# BMS-banana-rev1-0.net
KiCad netlist of a schematic drawn in EAGLE
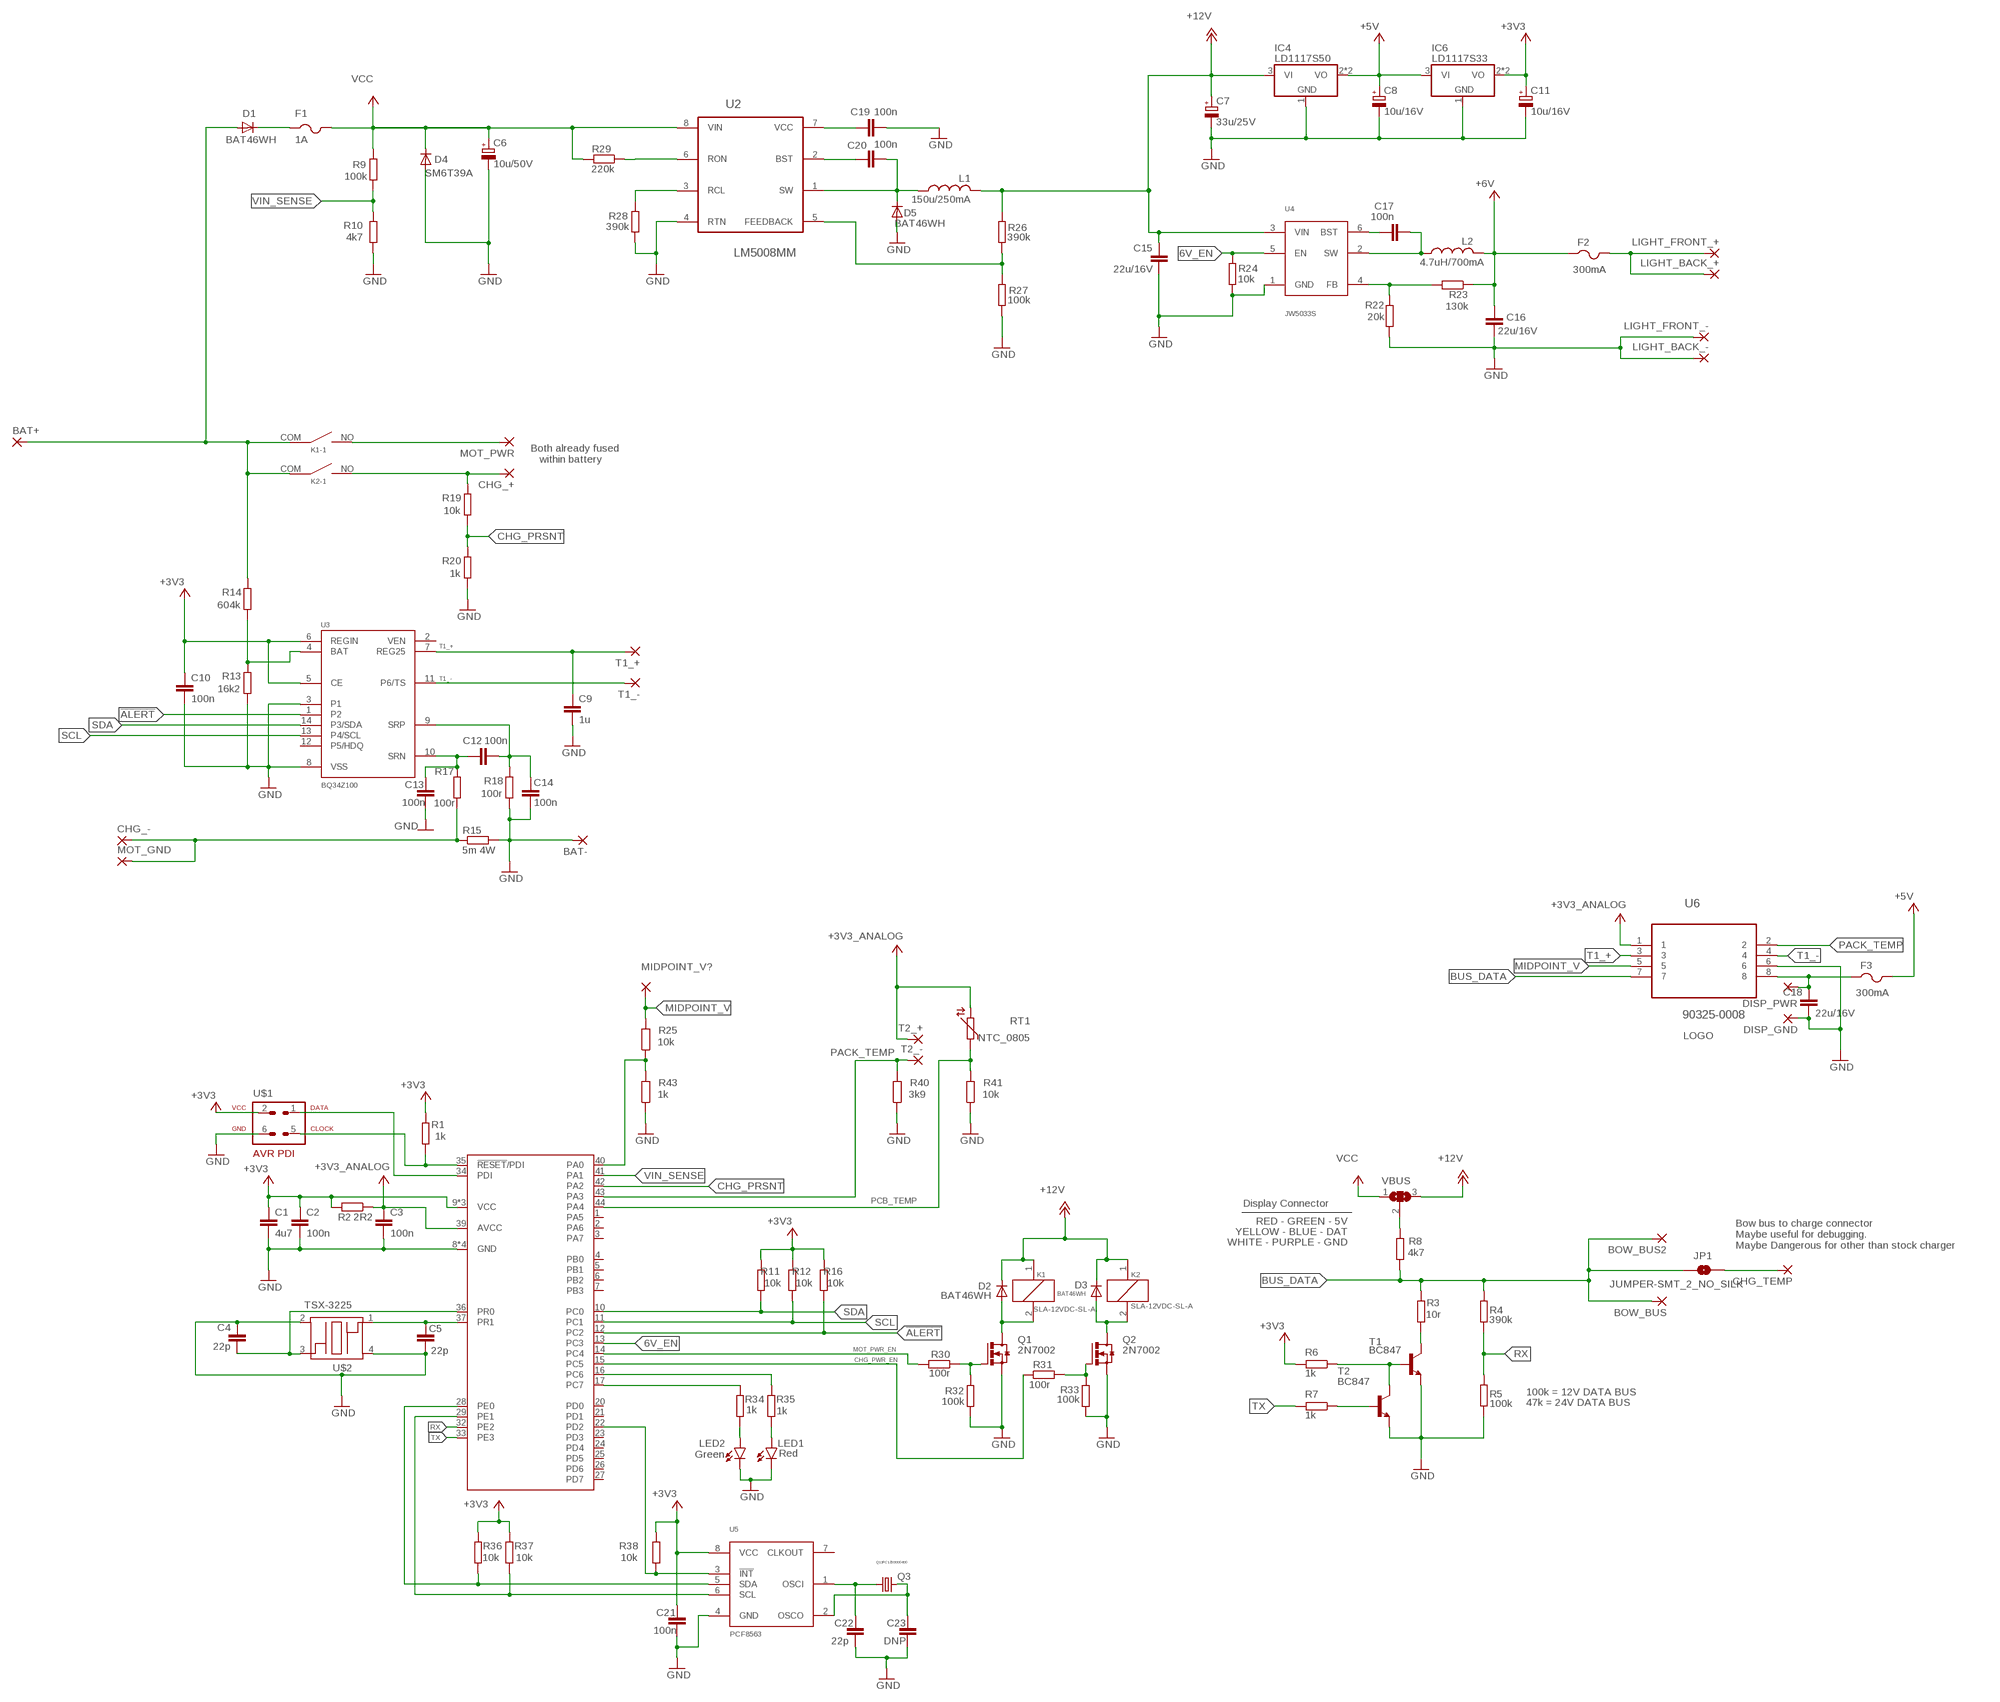
[diagram p0: schematic, sheet 1]

(export (version "E")
  (design (tool "Eeschema 10.0.6"))
  (components
    (comp (ref "BAT+")
      (value "3,81/2,1")
      (footprint "eagle-import:3,81_2,1")
      (libsource (lib "eagle-import") (part "3,81/2,1"))
    )
    (comp (ref "BAT-")
      (value "3,81/2,1")
      (footprint "eagle-import:3,81_2,1")
      (libsource (lib "eagle-import") (part "3,81/2,1"))
    )
    (comp (ref "BOW_BUS")
      (value "3,81/2,1")
      (footprint "eagle-import:3,81_2,1")
      (libsource (lib "eagle-import") (part "3,81/2,1"))
    )
    (comp (ref "BOW_BUS2")
      (value "2,54/0,8")
      (footprint "eagle-import:2,54_0,8")
      (libsource (lib "eagle-import") (part "2,54/0,8"))
    )
    (comp (ref "C1")
      (value "4u7")
      (footprint "eagle-import:C0805")
      (libsource (lib "eagle-import") (part "C-EUC0805"))
    )
    (comp (ref "C2")
      (value "100n")
      (footprint "eagle-import:C0805")
      (libsource (lib "eagle-import") (part "C-EUC0805"))
    )
    (comp (ref "C3")
      (value "100n")
      (footprint "eagle-import:C0805")
      (libsource (lib "eagle-import") (part "C-EUC0805"))
    )
    (comp (ref "C4")
      (value "22p")
      (footprint "eagle-import:C0805")
      (libsource (lib "eagle-import") (part "C-EUC0805"))
    )
    (comp (ref "C5")
      (value "22p")
      (footprint "eagle-import:C0805")
      (libsource (lib "eagle-import") (part "C-EUC0805"))
    )
    (comp (ref "C6")
      (value "10u/50V")
      (footprint "eagle-import:153CLV-0605")
      (libsource (lib "eagle-import") (part "CPOL-EU153CLV-0605"))
    )
    (comp (ref "C7")
      (value "33u/25V")
      (footprint "eagle-import:153CLV-0605")
      (libsource (lib "eagle-import") (part "CPOL-EU153CLV-0605"))
    )
    (comp (ref "C8")
      (value "10u/16V")
      (footprint "eagle-import:153CLV-0405")
      (libsource (lib "eagle-import") (part "CPOL-EU153CLV-0405"))
    )
    (comp (ref "C9")
      (value "1u")
      (footprint "eagle-import:C0805")
      (libsource (lib "eagle-import") (part "C-EUC0805"))
    )
    (comp (ref "C10")
      (value "100n")
      (footprint "eagle-import:C0805")
      (libsource (lib "eagle-import") (part "C-EUC0805"))
    )
    (comp (ref "C11")
      (value "10u/16V")
      (footprint "eagle-import:153CLV-0405")
      (libsource (lib "eagle-import") (part "CPOL-EU153CLV-0405"))
    )
    (comp (ref "C12")
      (value "100n")
      (footprint "eagle-import:C0805")
      (libsource (lib "eagle-import") (part "C-EUC0805"))
    )
    (comp (ref "C13")
      (value "100n")
      (footprint "eagle-import:C0805")
      (libsource (lib "eagle-import") (part "C-EUC0805"))
    )
    (comp (ref "C14")
      (value "100n")
      (footprint "eagle-import:C0805")
      (libsource (lib "eagle-import") (part "C-EUC0805"))
    )
    (comp (ref "C15")
      (value "22u/16V")
      (footprint "eagle-import:C0805")
      (libsource (lib "eagle-import") (part "C-EUC0805"))
    )
    (comp (ref "C16")
      (value "22u/16V")
      (footprint "eagle-import:C0805")
      (libsource (lib "eagle-import") (part "C-EUC0805"))
    )
    (comp (ref "C17")
      (value "100n")
      (footprint "eagle-import:C0805")
      (libsource (lib "eagle-import") (part "C-EUC0805"))
    )
    (comp (ref "C18")
      (value "22u/16V")
      (footprint "eagle-import:C0805")
      (libsource (lib "eagle-import") (part "C-EUC0805"))
    )
    (comp (ref "C19")
      (value "100n")
      (footprint "eagle-import:C0805")
      (libsource (lib "eagle-import") (part "C-EUC0805"))
    )
    (comp (ref "C20")
      (value "100n")
      (footprint "eagle-import:C0805")
      (libsource (lib "eagle-import") (part "C-EUC0805"))
    )
    (comp (ref "C21")
      (value "100n")
      (footprint "eagle-import:C0805")
      (libsource (lib "eagle-import") (part "C-EUC0805"))
    )
    (comp (ref "C22")
      (value "22p")
      (footprint "eagle-import:C0805")
      (libsource (lib "eagle-import") (part "C-EUC0805"))
    )
    (comp (ref "C23")
      (value "DNP")
      (footprint "eagle-import:C0805")
      (libsource (lib "eagle-import") (part "C-EUC0805"))
    )
    (comp (ref "CHG_+")
      (value "3,81/2,1")
      (footprint "eagle-import:3,81_2,1")
      (libsource (lib "eagle-import") (part "3,81/2,1"))
    )
    (comp (ref "CHG_-")
      (value "3,81/2,1")
      (footprint "eagle-import:3,81_2,1")
      (libsource (lib "eagle-import") (part "3,81/2,1"))
    )
    (comp (ref "CHG_TEMP")
      (value "3,81/2,1")
      (footprint "eagle-import:3,81_2,1")
      (libsource (lib "eagle-import") (part "3,81/2,1"))
    )
    (comp (ref "D1")
      (value "BAT46WH")
      (footprint "eagle-import:SMB")
      (libsource (lib "eagle-import") (part "DIODE-SMB"))
    )
    (comp (ref "D2")
      (value "BAT46WH")
      (footprint "eagle-import:SMB")
      (libsource (lib "eagle-import") (part "DIODE-SMB"))
    )
    (comp (ref "D3")
      (value "BAT46WH")
      (footprint "eagle-import:SMB")
      (libsource (lib "eagle-import") (part "DIODE-SMB"))
    )
    (comp (ref "D4")
      (value "SM6T39A")
      (footprint "eagle-import:SMB")
      (libsource (lib "eagle-import") (part "DIODE-SMB"))
    )
    (comp (ref "D5")
      (value "BAT46WH")
      (footprint "eagle-import:SOD323-W")
      (libsource (lib "eagle-import") (part "DIODE-SOD323-W"))
    )
    (comp (ref "DISP_GND")
      (value "2,54/0,8")
      (footprint "eagle-import:2,54_0,8")
      (libsource (lib "eagle-import") (part "2,54/0,8"))
    )
    (comp (ref "DISP_PWR")
      (value "2,54/0,8")
      (footprint "eagle-import:2,54_0,8")
      (libsource (lib "eagle-import") (part "2,54/0,8"))
    )
    (comp (ref "F1")
      (value "1A")
      (footprint "eagle-import:1812")
      (libsource (lib "eagle-import") (part "PTCFUSE-1812"))
    )
    (comp (ref "F2")
      (value "300mA")
      (footprint "eagle-import:1812")
      (libsource (lib "eagle-import") (part "PTCFUSE-1812"))
    )
    (comp (ref "F3")
      (value "300mA")
      (footprint "eagle-import:1812")
      (libsource (lib "eagle-import") (part "PTCFUSE-1812"))
    )
    (comp (ref "IC4")
      (value "LD1117S50")
      (footprint "eagle-import:SOT223")
      (libsource (lib "eagle-import") (part "LM340?-STST"))
    )
    (comp (ref "IC6")
      (value "LD1117S33")
      (footprint "eagle-import:SOT223")
      (libsource (lib "eagle-import") (part "LM340?-STST"))
    )
    (comp (ref "JP1")
      (value "JUMPER-SMT_2_NO_SILK")
      (footprint "eagle-import:SMT-JUMPER_2_NO_SILK")
      (libsource (lib "eagle-import") (part "JUMPER-SMT_2_NO_SILK"))
    )
    (comp (ref "K1")
      (value "SLA-12VDC-SL-A")
      (footprint "eagle-import:SLA-12VDC-SL-A")
      (libsource (lib "eagle-import") (part "SLA-12VDC-SL-A"))
    )
    (comp (ref "K2")
      (value "SLA-12VDC-SL-A")
      (footprint "eagle-import:SLA-12VDC-SL-A")
      (libsource (lib "eagle-import") (part "SLA-12VDC-SL-A"))
    )
    (comp (ref "L1")
      (value "150u/250mA")
      (footprint "eagle-import:POWER-CHOKE_WE-TPC")
      (libsource (lib "eagle-import") (part "L-USWE-TPC"))
    )
    (comp (ref "L2")
      (value "4.7uH/700mA")
      (footprint "eagle-import:L0805")
      (libsource (lib "eagle-import") (part "L_0805"))
    )
    (comp (ref "LED1")
      (value "Red")
      (footprint "eagle-import:CHIPLED_0805")
      (libsource (lib "eagle-import") (part "LEDCHIPLED_0805"))
    )
    (comp (ref "LED2")
      (value "Green")
      (footprint "eagle-import:CHIPLED_0805")
      (libsource (lib "eagle-import") (part "LEDCHIPLED_0805"))
    )
    (comp (ref "LIGHT_BACK_+")
      (value "2,54/0,8")
      (footprint "eagle-import:2,54_0,8")
      (libsource (lib "eagle-import") (part "2,54/0,8"))
    )
    (comp (ref "LIGHT_BACK_-")
      (value "2,54/0,8")
      (footprint "eagle-import:2,54_0,8")
      (libsource (lib "eagle-import") (part "2,54/0,8"))
    )
    (comp (ref "LIGHT_FRONT_+")
      (value "2,54/0,8")
      (footprint "eagle-import:2,54_0,8")
      (libsource (lib "eagle-import") (part "2,54/0,8"))
    )
    (comp (ref "LIGHT_FRONT_-")
      (value "2,54/0,8")
      (footprint "eagle-import:2,54_0,8")
      (libsource (lib "eagle-import") (part "2,54/0,8"))
    )
    (comp (ref "MIDPOINT_V?")
      (value "2,54/0,8")
      (footprint "eagle-import:2,54_0,8")
      (libsource (lib "eagle-import") (part "2,54/0,8"))
    )
    (comp (ref "MOT_GND")
      (value "3,81/2,1")
      (footprint "eagle-import:3,81_2,1")
      (libsource (lib "eagle-import") (part "3,81/2,1"))
    )
    (comp (ref "MOT_PWR")
      (value "3,81/2,1")
      (footprint "eagle-import:3,81_2,1")
      (libsource (lib "eagle-import") (part "3,81/2,1"))
    )
    (comp (ref "Q1")
      (value "2N7002")
      (footprint "eagle-import:SOT-23")
      (libsource (lib "eagle-import") (part "2N7002"))
    )
    (comp (ref "Q2")
      (value "2N7002")
      (footprint "eagle-import:SOT-23")
      (libsource (lib "eagle-import") (part "2N7002"))
    )
    (comp (ref "Q3")
      (value "Q13FC1350000400")
      (footprint "eagle-import:CRYSTAL_3215")
      (libsource (lib "eagle-import") (part "Q13FC1350000400"))
    )
    (comp (ref "R1")
      (value "1k")
      (footprint "eagle-import:R0805")
      (libsource (lib "eagle-import") (part "R-EU_R0805"))
    )
    (comp (ref "R2")
      (value "2R2")
      (footprint "eagle-import:R0805")
      (libsource (lib "eagle-import") (part "R-EU_R0805"))
    )
    (comp (ref "R3")
      (value "10r")
      (footprint "eagle-import:R0805")
      (libsource (lib "eagle-import") (part "R-EU_R0805"))
    )
    (comp (ref "R4")
      (value "390k")
      (footprint "eagle-import:R0805")
      (libsource (lib "eagle-import") (part "R-EU_R0805"))
    )
    (comp (ref "R5")
      (value "100k")
      (footprint "eagle-import:R0805")
      (libsource (lib "eagle-import") (part "R-EU_R0805"))
    )
    (comp (ref "R6")
      (value "1k")
      (footprint "eagle-import:R0805")
      (libsource (lib "eagle-import") (part "R-EU_R0805"))
    )
    (comp (ref "R7")
      (value "1k")
      (footprint "eagle-import:R0805")
      (libsource (lib "eagle-import") (part "R-EU_R0805"))
    )
    (comp (ref "R8")
      (value "4k7")
      (footprint "eagle-import:R0805")
      (libsource (lib "eagle-import") (part "R-EU_R0805"))
    )
    (comp (ref "R9")
      (value "100k")
      (footprint "eagle-import:R0805")
      (libsource (lib "eagle-import") (part "R-EU_R0805"))
    )
    (comp (ref "R10")
      (value "4k7")
      (footprint "eagle-import:R0805")
      (libsource (lib "eagle-import") (part "R-EU_R0805"))
    )
    (comp (ref "R11")
      (value "10k")
      (footprint "eagle-import:R0805")
      (libsource (lib "eagle-import") (part "R-EU_R0805"))
    )
    (comp (ref "R12")
      (value "10k")
      (footprint "eagle-import:R0805")
      (libsource (lib "eagle-import") (part "R-EU_R0805"))
    )
    (comp (ref "R13")
      (value "16k2")
      (footprint "eagle-import:R0805")
      (libsource (lib "eagle-import") (part "R-EU_R0805"))
    )
    (comp (ref "R14")
      (value "604k")
      (footprint "eagle-import:R0805")
      (libsource (lib "eagle-import") (part "R-EU_R0805"))
    )
    (comp (ref "R15")
      (value "5m 4W")
      (footprint "eagle-import:R2728")
      (libsource (lib "eagle-import") (part "SHUNT_2728"))
    )
    (comp (ref "R16")
      (value "10k")
      (footprint "eagle-import:R0805")
      (libsource (lib "eagle-import") (part "R-EU_R0805"))
    )
    (comp (ref "R17")
      (value "100r")
      (footprint "eagle-import:R0805")
      (libsource (lib "eagle-import") (part "R-EU_R0805"))
    )
    (comp (ref "R18")
      (value "100r")
      (footprint "eagle-import:R0805")
      (libsource (lib "eagle-import") (part "R-EU_R0805"))
    )
    (comp (ref "R19")
      (value "10k")
      (footprint "eagle-import:R0805")
      (libsource (lib "eagle-import") (part "R-EU_R0805"))
    )
    (comp (ref "R20")
      (value "1k")
      (footprint "eagle-import:R0805")
      (libsource (lib "eagle-import") (part "R-EU_R0805"))
    )
    (comp (ref "R22")
      (value "20k")
      (footprint "eagle-import:R0805")
      (libsource (lib "eagle-import") (part "R-EU_R0805"))
    )
    (comp (ref "R23")
      (value "130k")
      (footprint "eagle-import:R0805")
      (libsource (lib "eagle-import") (part "R-EU_R0805"))
    )
    (comp (ref "R24")
      (value "10k")
      (footprint "eagle-import:R0805")
      (libsource (lib "eagle-import") (part "R-EU_R0805"))
    )
    (comp (ref "R25")
      (value "10k")
      (footprint "eagle-import:R0805")
      (libsource (lib "eagle-import") (part "R-EU_R0805"))
    )
    (comp (ref "R26")
      (value "390k")
      (footprint "eagle-import:R0805")
      (libsource (lib "eagle-import") (part "R-EU_R0805"))
    )
    (comp (ref "R27")
      (value "100k")
      (footprint "eagle-import:R0805")
      (libsource (lib "eagle-import") (part "R-EU_R0805"))
    )
    (comp (ref "R28")
      (value "390k")
      (footprint "eagle-import:R0805")
      (libsource (lib "eagle-import") (part "R-EU_R0805"))
    )
    (comp (ref "R29")
      (value "220k")
      (footprint "eagle-import:R0805")
      (libsource (lib "eagle-import") (part "R-EU_R0805"))
    )
    (comp (ref "R30")
      (value "100r")
      (footprint "eagle-import:R0805")
      (libsource (lib "eagle-import") (part "R-EU_R0805"))
    )
    (comp (ref "R31")
      (value "100r")
      (footprint "eagle-import:R0805")
      (libsource (lib "eagle-import") (part "R-EU_R0805"))
    )
    (comp (ref "R32")
      (value "100k")
      (footprint "eagle-import:R0805")
      (libsource (lib "eagle-import") (part "R-EU_R0805"))
    )
    (comp (ref "R33")
      (value "100k")
      (footprint "eagle-import:R0805")
      (libsource (lib "eagle-import") (part "R-EU_R0805"))
    )
    (comp (ref "R34")
      (value "1k")
      (footprint "eagle-import:R0805")
      (libsource (lib "eagle-import") (part "R-EU_R0805"))
    )
    (comp (ref "R35")
      (value "1k")
      (footprint "eagle-import:R0805")
      (libsource (lib "eagle-import") (part "R-EU_R0805"))
    )
    (comp (ref "R36")
      (value "10k")
      (footprint "eagle-import:R0805")
      (libsource (lib "eagle-import") (part "R-EU_R0805"))
    )
    (comp (ref "R37")
      (value "10k")
      (footprint "eagle-import:R0805")
      (libsource (lib "eagle-import") (part "R-EU_R0805"))
    )
    (comp (ref "R38")
      (value "10k")
      (footprint "eagle-import:R0805")
      (libsource (lib "eagle-import") (part "R-EU_R0805"))
    )
    (comp (ref "R40")
      (value "3k9")
      (footprint "eagle-import:R0805")
      (libsource (lib "eagle-import") (part "R-EU_R0805"))
    )
    (comp (ref "R41")
      (value "10k")
      (footprint "eagle-import:R0805")
      (libsource (lib "eagle-import") (part "R-EU_R0805"))
    )
    (comp (ref "R43")
      (value "1k")
      (footprint "eagle-import:R0805")
      (libsource (lib "eagle-import") (part "R-EU_R0805"))
    )
    (comp (ref "RT1")
      (value "NTC_0805")
      (footprint "eagle-import:R0805")
      (libsource (lib "eagle-import") (part "NTC_0805"))
    )
    (comp (ref "T1")
      (value "BC847")
      (footprint "eagle-import:SOT23")
      (libsource (lib "eagle-import") (part "BC847"))
    )
    (comp (ref "T1_+")
      (value "2,54/0,8")
      (footprint "eagle-import:2,54_0,8")
      (libsource (lib "eagle-import") (part "2,54/0,8"))
    )
    (comp (ref "T1_-")
      (value "2,54/0,8")
      (footprint "eagle-import:2,54_0,8")
      (libsource (lib "eagle-import") (part "2,54/0,8"))
    )
    (comp (ref "T2")
      (value "BC847")
      (footprint "eagle-import:SOT23")
      (libsource (lib "eagle-import") (part "BC847"))
    )
    (comp (ref "T2_+")
      (value "2,54/0,8")
      (footprint "eagle-import:2,54_0,8")
      (libsource (lib "eagle-import") (part "2,54/0,8"))
    )
    (comp (ref "T2_-")
      (value "2,54/0,8")
      (footprint "eagle-import:2,54_0,8")
      (libsource (lib "eagle-import") (part "2,54/0,8"))
    )
    (comp (ref "U$1")
      (value "AVR-PDIVERT")
      (footprint "eagle-import:AVR-ISP-6")
      (libsource (lib "eagle-import") (part "AVR-PDIVERT"))
    )
    (comp (ref "U$2")
      (value "TSX-3225")
      (footprint "eagle-import:TSX-3225")
      (libsource (lib "eagle-import") (part "TSX-3225"))
    )
    (comp (ref "U$4")
      (value "AFROBOTICLOGOAFROBOTICLOGO_SMALL")
      (footprint "eagle-import:AFROBOTICLOGOSMALL")
      (libsource (lib "eagle-import") (part "AFROBOTICLOGOAFROBOTICLOGO_SMALL"))
    )
    (comp (ref "U1")
      (value "ATXMEGA32A4U-AU")
      (footprint "eagle-import:TQFP-44A-44")
      (libsource (lib "eagle-import") (part "ATXMEGA32A4U-AU"))
    )
    (comp (ref "U2")
      (value "LM5008MM")
      (footprint "eagle-import:SOP65P490X109-8N")
      (libsource (lib "eagle-import") (part "LM5008MM"))
    )
    (comp (ref "U3")
      (value "BQ34Z100")
      (footprint "eagle-import:PW_R-PDSO-G14")
      (libsource (lib "eagle-import") (part "BQ34Z100"))
    )
    (comp (ref "U4")
      (value "JW5033S")
      (footprint "eagle-import:SOT23-6")
      (libsource (lib "eagle-import") (part "JW5033S"))
    )
    (comp (ref "U5")
      (value "PCF8563")
      (footprint "eagle-import:SO08")
      (libsource (lib "eagle-import") (part "PCF8563"))
    )
    (comp (ref "U6")
      (value "90325-0008")
      (footprint "eagle-import:MOLEX_90325-0008")
      (libsource (lib "eagle-import") (part "90325-0008"))
    )
    (comp (ref "VBUS")
      (value "SJ2W")
      (footprint "eagle-import:SJ_2")
      (libsource (lib "eagle-import") (part "SJ2W"))
    )
  )
  (nets
    (net (code "1") (name "+3V3") (class "Default")
      (node (ref "C1") (pin "1") (pinfunction "1_1") (pintype "passive"))
      (node (ref "C10") (pin "1") (pinfunction "1_1") (pintype "passive"))
      (node (ref "C11") (pin "+") (pinfunction "+_+") (pintype "passive"))
      (node (ref "C2") (pin "1") (pinfunction "1_1") (pintype "passive"))
      (node (ref "C21") (pin "2") (pinfunction "2_2") (pintype "passive"))
      (node (ref "IC6") (pin "2") (pinfunction "VO_2") (pintype "passive"))
      (node (ref "IC6") (pin "4") (pinfunction "VO_4") (pintype "passive"))
      (node (ref "R1") (pin "2") (pinfunction "2_2") (pintype "passive"))
      (node (ref "R11") (pin "2") (pinfunction "2_2") (pintype "passive"))
      (node (ref "R12") (pin "2") (pinfunction "2_2") (pintype "passive"))
      (node (ref "R16") (pin "2") (pinfunction "2_2") (pintype "passive"))
      (node (ref "R2") (pin "2") (pinfunction "2_2") (pintype "passive"))
      (node (ref "R36") (pin "2") (pinfunction "2_2") (pintype "passive"))
      (node (ref "R37") (pin "2") (pinfunction "2_2") (pintype "passive"))
      (node (ref "R38") (pin "2") (pinfunction "2_2") (pintype "passive"))
      (node (ref "R6") (pin "2") (pinfunction "2_2") (pintype "passive"))
      (node (ref "U$1") (pin "2") (pinfunction "2_2") (pintype "passive"))
      (node (ref "U1") (pin "19") (pinfunction "VCC_19") (pintype "power_in"))
      (node (ref "U1") (pin "31") (pinfunction "VCC_31") (pintype "power_in"))
      (node (ref "U1") (pin "9") (pinfunction "VCC_9") (pintype "power_in"))
      (node (ref "U3") (pin "5") (pinfunction "CE_5") (pintype "bidirectional"))
      (node (ref "U3") (pin "6") (pinfunction "REGIN_6") (pintype "bidirectional"))
      (node (ref "U5") (pin "8") (pinfunction "VCC_8") (pintype "power_in"))
    )
    (net (code "2") (name "+3V3_ANALOG") (class "Default")
      (node (ref "C3") (pin "1") (pinfunction "1_1") (pintype "passive"))
      (node (ref "R2") (pin "1") (pinfunction "1_1") (pintype "passive"))
      (node (ref "RT1") (pin "2") (pinfunction "2_2") (pintype "passive"))
      (node (ref "T2_+") (pin "1") (pinfunction "P_1") (pintype "passive"))
      (node (ref "U1") (pin "39") (pinfunction "AVCC_39") (pintype "power_in"))
      (node (ref "U6") (pin "1") (pinfunction "1_1") (pintype "passive"))
    )
    (net (code "3") (name "+5V") (class "Default")
      (node (ref "C8") (pin "+") (pinfunction "+_+") (pintype "passive"))
      (node (ref "F3") (pin "2") (pinfunction "2_2") (pintype "passive"))
      (node (ref "IC4") (pin "2") (pinfunction "VO_2") (pintype "passive"))
      (node (ref "IC4") (pin "4") (pinfunction "VO_4") (pintype "passive"))
      (node (ref "IC6") (pin "3") (pinfunction "VI_3") (pintype "input"))
    )
    (net (code "4") (name "+6V") (class "Default")
      (node (ref "C16") (pin "2") (pinfunction "2_2") (pintype "passive"))
      (node (ref "F2") (pin "1") (pinfunction "1_1") (pintype "passive"))
      (node (ref "L2") (pin "2") (pinfunction "2_2") (pintype "passive"))
      (node (ref "R23") (pin "1") (pinfunction "1_1") (pintype "passive"))
    )
    (net (code "5") (name "+12V") (class "Default")
      (node (ref "C15") (pin "2") (pinfunction "2_2") (pintype "passive"))
      (node (ref "C7") (pin "+") (pinfunction "+_+") (pintype "passive"))
      (node (ref "D2") (pin "C") (pinfunction "C_C") (pintype "passive"))
      (node (ref "D3") (pin "C") (pinfunction "C_C") (pintype "passive"))
      (node (ref "IC4") (pin "3") (pinfunction "VI_3") (pintype "input"))
      (node (ref "K1") (pin "1") (pinfunction "1_1") (pintype "bidirectional"))
      (node (ref "K2") (pin "1") (pinfunction "1_1") (pintype "bidirectional"))
      (node (ref "L1") (pin "2") (pinfunction "2_2") (pintype "passive"))
      (node (ref "R26") (pin "2") (pinfunction "2_2") (pintype "passive"))
      (node (ref "U4") (pin "3") (pinfunction "VIN_3") (pintype "power_in"))
      (node (ref "VBUS") (pin "3") (pinfunction "3_3") (pintype "passive"))
    )
    (net (code "6") (name "/CHG_PWR_EN") (class "Default")
      (node (ref "R31") (pin "1") (pinfunction "1_1") (pintype "passive"))
      (node (ref "U1") (pin "15") (pinfunction "PC5_15") (pintype "bidirectional"))
    )
    (net (code "7") (name "/MOT_PWR_EN") (class "Default")
      (node (ref "R30") (pin "2") (pinfunction "2_2") (pintype "passive"))
      (node (ref "U1") (pin "14") (pinfunction "PC4_14") (pintype "bidirectional"))
    )
    (net (code "8") (name "/PCB_TEMP") (class "Default")
      (node (ref "R41") (pin "2") (pinfunction "2_2") (pintype "passive"))
      (node (ref "RT1") (pin "1") (pinfunction "1_1") (pintype "passive"))
      (node (ref "U1") (pin "44") (pinfunction "PA4_44") (pintype "bidirectional"))
    )
    (net (code "9") (name "/~{ALERT}") (class "Default")
      (node (ref "R16") (pin "1") (pinfunction "1_1") (pintype "passive"))
      (node (ref "U1") (pin "12") (pinfunction "PC2_12") (pintype "bidirectional"))
      (node (ref "U3") (pin "1") (pinfunction "P2_1") (pintype "bidirectional"))
    )
    (net (code "10") (name "6V_EN") (class "Default")
      (node (ref "R24") (pin "2") (pinfunction "2_2") (pintype "passive"))
      (node (ref "U1") (pin "13") (pinfunction "PC3_13") (pintype "bidirectional"))
      (node (ref "U4") (pin "5") (pinfunction "EN_5") (pintype "bidirectional"))
    )
    (net (code "11") (name "BUS_DATA") (class "Default")
      (node (ref "BOW_BUS") (pin "1") (pinfunction "P_1") (pintype "passive"))
      (node (ref "BOW_BUS2") (pin "1") (pinfunction "P_1") (pintype "passive"))
      (node (ref "JP1") (pin "1") (pinfunction "1_1") (pintype "passive"))
      (node (ref "R3") (pin "2") (pinfunction "2_2") (pintype "passive"))
      (node (ref "R4") (pin "2") (pinfunction "2_2") (pintype "passive"))
      (node (ref "R8") (pin "1") (pinfunction "1_1") (pintype "passive"))
      (node (ref "U6") (pin "7") (pinfunction "7_7") (pintype "passive"))
    )
    (net (code "12") (name "CHG_PRSNT") (class "Default")
      (node (ref "R19") (pin "1") (pinfunction "1_1") (pintype "passive"))
      (node (ref "R20") (pin "2") (pinfunction "2_2") (pintype "passive"))
      (node (ref "U1") (pin "42") (pinfunction "PA2_42") (pintype "bidirectional"))
    )
    (net (code "13") (name "GND") (class "Default")
      (node (ref "BAT-") (pin "1") (pinfunction "P_1") (pintype "passive"))
      (node (ref "C1") (pin "2") (pinfunction "2_2") (pintype "passive"))
      (node (ref "C10") (pin "2") (pinfunction "2_2") (pintype "passive"))
      (node (ref "C11") (pin "-") (pinfunction "-_-") (pintype "passive"))
      (node (ref "C13") (pin "1") (pinfunction "1_1") (pintype "passive"))
      (node (ref "C14") (pin "1") (pinfunction "1_1") (pintype "passive"))
      (node (ref "C15") (pin "1") (pinfunction "1_1") (pintype "passive"))
      (node (ref "C16") (pin "1") (pinfunction "1_1") (pintype "passive"))
      (node (ref "C18") (pin "1") (pinfunction "1_1") (pintype "passive"))
      (node (ref "C19") (pin "2") (pinfunction "2_2") (pintype "passive"))
      (node (ref "C2") (pin "2") (pinfunction "2_2") (pintype "passive"))
      (node (ref "C21") (pin "1") (pinfunction "1_1") (pintype "passive"))
      (node (ref "C22") (pin "1") (pinfunction "1_1") (pintype "passive"))
      (node (ref "C23") (pin "1") (pinfunction "1_1") (pintype "passive"))
      (node (ref "C3") (pin "2") (pinfunction "2_2") (pintype "passive"))
      (node (ref "C4") (pin "1") (pinfunction "1_1") (pintype "passive"))
      (node (ref "C5") (pin "2") (pinfunction "2_2") (pintype "passive"))
      (node (ref "C6") (pin "-") (pinfunction "-_-") (pintype "passive"))
      (node (ref "C7") (pin "-") (pinfunction "-_-") (pintype "passive"))
      (node (ref "C8") (pin "-") (pinfunction "-_-") (pintype "passive"))
      (node (ref "C9") (pin "2") (pinfunction "2_2") (pintype "passive"))
      (node (ref "D4") (pin "A") (pinfunction "A_A") (pintype "passive"))
      (node (ref "D5") (pin "A") (pinfunction "A_A") (pintype "passive"))
      (node (ref "DISP_GND") (pin "1") (pinfunction "P_1") (pintype "passive"))
      (node (ref "IC4") (pin "1") (pinfunction "GND_1") (pintype "passive"))
      (node (ref "IC6") (pin "1") (pinfunction "GND_1") (pintype "passive"))
      (node (ref "LED1") (pin "C") (pinfunction "C_C") (pintype "passive"))
      (node (ref "LED2") (pin "C") (pinfunction "C_C") (pintype "passive"))
      (node (ref "LIGHT_BACK_-") (pin "1") (pinfunction "P_1") (pintype "passive"))
      (node (ref "LIGHT_FRONT_-") (pin "1") (pinfunction "P_1") (pintype "passive"))
      (node (ref "Q1") (pin "2") (pinfunction "S_2") (pintype "passive"))
      (node (ref "Q2") (pin "2") (pinfunction "S_2") (pintype "passive"))
      (node (ref "R10") (pin "1") (pinfunction "1_1") (pintype "passive"))
      (node (ref "R13") (pin "1") (pinfunction "1_1") (pintype "passive"))
      (node (ref "R15") (pin "P$2") (pinfunction "2_P$2") (pintype "passive"))
      (node (ref "R18") (pin "1") (pinfunction "1_1") (pintype "passive"))
      (node (ref "R20") (pin "1") (pinfunction "1_1") (pintype "passive"))
      (node (ref "R22") (pin "1") (pinfunction "1_1") (pintype "passive"))
      (node (ref "R24") (pin "1") (pinfunction "1_1") (pintype "passive"))
      (node (ref "R27") (pin "1") (pinfunction "1_1") (pintype "passive"))
      (node (ref "R28") (pin "1") (pinfunction "1_1") (pintype "passive"))
      (node (ref "R32") (pin "2") (pinfunction "2_2") (pintype "passive"))
      (node (ref "R33") (pin "2") (pinfunction "2_2") (pintype "passive"))
      (node (ref "R40") (pin "1") (pinfunction "1_1") (pintype "passive"))
      (node (ref "R41") (pin "1") (pinfunction "1_1") (pintype "passive"))
      (node (ref "R43") (pin "1") (pinfunction "1_1") (pintype "passive"))
      (node (ref "R5") (pin "1") (pinfunction "1_1") (pintype "passive"))
      (node (ref "T1") (pin "2") (pinfunction "E_2") (pintype "passive"))
      (node (ref "T2") (pin "2") (pinfunction "E_2") (pintype "passive"))
      (node (ref "U$1") (pin "6") (pinfunction "6_6") (pintype "passive"))
      (node (ref "U$2") (pin "2") (pinfunction "GND_2_2") (pintype "bidirectional"))
      (node (ref "U$2") (pin "4") (pinfunction "GND_4_4") (pintype "bidirectional"))
      (node (ref "U1") (pin "18") (pinfunction "GND_18") (pintype "power_in"))
      (node (ref "U1") (pin "30") (pinfunction "GND_30") (pintype "power_in"))
      (node (ref "U1") (pin "38") (pinfunction "GND_38") (pintype "power_in"))
      (node (ref "U1") (pin "8") (pinfunction "GND_8") (pintype "power_in"))
      (node (ref "U2") (pin "4") (pinfunction "RTN_4") (pintype "passive"))
      (node (ref "U3") (pin "3") (pinfunction "P1_3") (pintype "bidirectional"))
      (node (ref "U3") (pin "8") (pinfunction "VSS_8") (pintype "bidirectional"))
      (node (ref "U4") (pin "1") (pinfunction "GND_1") (pintype "power_in"))
      (node (ref "U5") (pin "4") (pinfunction "GND_4") (pintype "power_in"))
      (node (ref "U6") (pin "6") (pinfunction "6_6") (pintype "passive"))
    )
    (net (code "14") (name "MIDPOINT_V") (class "Default")
      (node (ref "MIDPOINT_V?") (pin "1") (pinfunction "P_1") (pintype "passive"))
      (node (ref "R25") (pin "2") (pinfunction "2_2") (pintype "passive"))
      (node (ref "U6") (pin "5") (pinfunction "5_5") (pintype "passive"))
    )
    (net (code "15") (name "Net-(BAT+-P)") (class "Default")
      (node (ref "BAT+") (pin "1") (pinfunction "P_1") (pintype "passive"))
      (node (ref "D1") (pin "A") (pinfunction "A_A") (pintype "passive"))
      (node (ref "K1") (pin "COM") (pinfunction "COM_COM") (pintype "bidirectional"))
      (node (ref "K2") (pin "COM") (pinfunction "COM_COM") (pintype "bidirectional"))
      (node (ref "R14") (pin "2") (pinfunction "2_2") (pintype "passive"))
    )
    (net (code "16") (name "Net-(CHG_+-P)") (class "Default")
      (node (ref "CHG_+") (pin "1") (pinfunction "P_1") (pintype "passive"))
      (node (ref "K2") (pin "NO") (pinfunction "NO_NO") (pintype "bidirectional"))
      (node (ref "R19") (pin "2") (pinfunction "2_2") (pintype "passive"))
    )
    (net (code "17") (name "Net-(CHG_--P)") (class "Default")
      (node (ref "CHG_-") (pin "1") (pinfunction "P_1") (pintype "passive"))
      (node (ref "MOT_GND") (pin "1") (pinfunction "P_1") (pintype "passive"))
      (node (ref "R15") (pin "P$1") (pinfunction "1_P$1") (pintype "passive"))
      (node (ref "R17") (pin "1") (pinfunction "1_1") (pintype "passive"))
    )
    (net (code "18") (name "Net-(CHG_TEMP-P)") (class "Default")
      (node (ref "CHG_TEMP") (pin "1") (pinfunction "P_1") (pintype "passive"))
      (node (ref "JP1") (pin "2") (pinfunction "2_2") (pintype "passive"))
    )
    (net (code "19") (name "Net-(D1-PadC)") (class "Default")
      (node (ref "D1") (pin "C") (pinfunction "C_C") (pintype "passive"))
      (node (ref "F1") (pin "1") (pinfunction "1_1") (pintype "passive"))
    )
    (net (code "20") (name "Net-(DISP_PWR-P)") (class "Default")
      (node (ref "C18") (pin "2") (pinfunction "2_2") (pintype "passive"))
      (node (ref "DISP_PWR") (pin "1") (pinfunction "P_1") (pintype "passive"))
      (node (ref "F3") (pin "1") (pinfunction "1_1") (pintype "passive"))
      (node (ref "U6") (pin "8") (pinfunction "8_8") (pintype "passive"))
    )
    (net (code "21") (name "Net-(LED1-PadA)") (class "Default")
      (node (ref "LED1") (pin "A") (pinfunction "A_A") (pintype "passive"))
      (node (ref "R35") (pin "1") (pinfunction "1_1") (pintype "passive"))
    )
    (net (code "22") (name "Net-(LED2-PadA)") (class "Default")
      (node (ref "LED2") (pin "A") (pinfunction "A_A") (pintype "passive"))
      (node (ref "R34") (pin "1") (pinfunction "1_1") (pintype "passive"))
    )
    (net (code "23") (name "Net-(LIGHT_BACK_+-P)") (class "Default")
      (node (ref "F2") (pin "2") (pinfunction "2_2") (pintype "passive"))
      (node (ref "LIGHT_BACK_+") (pin "1") (pinfunction "P_1") (pintype "passive"))
      (node (ref "LIGHT_FRONT_+") (pin "1") (pinfunction "P_1") (pintype "passive"))
    )
    (net (code "24") (name "Net-(MOT_PWR-P)") (class "Default")
      (node (ref "K1") (pin "NO") (pinfunction "NO_NO") (pintype "bidirectional"))
      (node (ref "MOT_PWR") (pin "1") (pinfunction "P_1") (pintype "passive"))
    )
    (net (code "25") (name "Net-(Q1-D)") (class "Default")
      (node (ref "D2") (pin "A") (pinfunction "A_A") (pintype "passive"))
      (node (ref "K1") (pin "2") (pinfunction "2_2") (pintype "bidirectional"))
      (node (ref "Q1") (pin "3") (pinfunction "D_3") (pintype "passive"))
    )
    (net (code "26") (name "Net-(Q1-G)") (class "Default")
      (node (ref "Q1") (pin "1") (pinfunction "G_1") (pintype "passive"))
      (node (ref "R30") (pin "1") (pinfunction "1_1") (pintype "passive"))
      (node (ref "R32") (pin "1") (pinfunction "1_1") (pintype "passive"))
    )
    (net (code "27") (name "Net-(Q2-D)") (class "Default")
      (node (ref "D3") (pin "A") (pinfunction "A_A") (pintype "passive"))
      (node (ref "K2") (pin "2") (pinfunction "2_2") (pintype "bidirectional"))
      (node (ref "Q2") (pin "3") (pinfunction "D_3") (pintype "passive"))
    )
    (net (code "28") (name "Net-(Q2-G)") (class "Default")
      (node (ref "Q2") (pin "1") (pinfunction "G_1") (pintype "passive"))
      (node (ref "R31") (pin "2") (pinfunction "2_2") (pintype "passive"))
      (node (ref "R33") (pin "1") (pinfunction "1_1") (pintype "passive"))
    )
    (net (code "29") (name "Net-(Q3-1)") (class "Default")
      (node (ref "C22") (pin "2") (pinfunction "2_2") (pintype "passive"))
      (node (ref "Q3") (pin "P$1") (pinfunction "1_P$1") (pintype "passive"))
      (node (ref "U5") (pin "1") (pinfunction "OSCI_1") (pintype "bidirectional"))
    )
    (net (code "30") (name "Net-(Q3-2)") (class "Default")
      (node (ref "C23") (pin "2") (pinfunction "2_2") (pintype "passive"))
      (node (ref "Q3") (pin "P$2") (pinfunction "2_P$2") (pintype "passive"))
      (node (ref "U5") (pin "2") (pinfunction "OSCO_2") (pintype "bidirectional"))
    )
    (net (code "31") (name "Net-(R8-Pad2)") (class "Default")
      (node (ref "R8") (pin "2") (pinfunction "2_2") (pintype "passive"))
      (node (ref "VBUS") (pin "2") (pinfunction "2_2") (pintype "passive"))
    )
    (net (code "32") (name "Net-(T1-B)") (class "Default")
      (node (ref "R6") (pin "1") (pinfunction "1_1") (pintype "passive"))
      (node (ref "T1") (pin "1") (pinfunction "B_1") (pintype "passive"))
      (node (ref "T2") (pin "3") (pinfunction "C_3") (pintype "passive"))
    )
    (net (code "33") (name "Net-(T1-C)") (class "Default")
      (node (ref "R3") (pin "1") (pinfunction "1_1") (pintype "passive"))
      (node (ref "T1") (pin "3") (pinfunction "C_3") (pintype "passive"))
    )
    (net (code "34") (name "Net-(T2-B)") (class "Default")
      (node (ref "R7") (pin "1") (pinfunction "1_1") (pintype "passive"))
      (node (ref "T2") (pin "1") (pinfunction "B_1") (pintype "passive"))
    )
    (net (code "35") (name "Net-(U$2-XTALIN)") (class "Default")
      (node (ref "C5") (pin "1") (pinfunction "1_1") (pintype "passive"))
      (node (ref "U$2") (pin "1") (pinfunction "XTALIN_1") (pintype "bidirectional"))
      (node (ref "U1") (pin "37") (pinfunction "PR1_37") (pintype "bidirectional"))
    )
    (net (code "36") (name "Net-(U$2-XTALOUT)") (class "Default")
      (node (ref "C4") (pin "2") (pinfunction "2_2") (pintype "passive"))
      (node (ref "U$2") (pin "3") (pinfunction "XTALOUT_3") (pintype "bidirectional"))
      (node (ref "U1") (pin "36") (pinfunction "PR0_36") (pintype "bidirectional"))
    )
    (net (code "37") (name "Net-(U1-PA0)") (class "Default")
      (node (ref "R25") (pin "1") (pinfunction "1_1") (pintype "passive"))
      (node (ref "R43") (pin "2") (pinfunction "2_2") (pintype "passive"))
      (node (ref "U1") (pin "40") (pinfunction "PA0_40") (pintype "bidirectional"))
    )
    (net (code "38") (name "Net-(U1-PC6)") (class "Default")
      (node (ref "R35") (pin "2") (pinfunction "2_2") (pintype "passive"))
      (node (ref "U1") (pin "16") (pinfunction "PC6_16") (pintype "bidirectional"))
    )
    (net (code "39") (name "Net-(U1-PC7)") (class "Default")
      (node (ref "R34") (pin "2") (pinfunction "2_2") (pintype "passive"))
      (node (ref "U1") (pin "17") (pinfunction "PC7_17") (pintype "bidirectional"))
    )
    (net (code "40") (name "Net-(U1-PD2)") (class "Default")
      (node (ref "R38") (pin "1") (pinfunction "1_1") (pintype "passive"))
      (node (ref "U1") (pin "22") (pinfunction "PD2_22") (pintype "bidirectional"))
      (node (ref "U5") (pin "3") (pinfunction "~{INT}_3") (pintype "bidirectional"))
    )
    (net (code "41") (name "Net-(U1-PDI)") (class "Default")
      (node (ref "U$1") (pin "1") (pinfunction "1_1") (pintype "passive"))
      (node (ref "U1") (pin "34") (pinfunction "PDI_34") (pintype "bidirectional"))
    )
    (net (code "42") (name "Net-(U1-PE0)") (class "Default")
      (node (ref "R36") (pin "1") (pinfunction "1_1") (pintype "passive"))
      (node (ref "U1") (pin "28") (pinfunction "PE0_28") (pintype "bidirectional"))
      (node (ref "U5") (pin "5") (pinfunction "SDA_5") (pintype "bidirectional"))
    )
    (net (code "43") (name "Net-(U1-PE1)") (class "Default")
      (node (ref "R37") (pin "1") (pinfunction "1_1") (pintype "passive"))
      (node (ref "U1") (pin "29") (pinfunction "PE1_29") (pintype "bidirectional"))
      (node (ref "U5") (pin "6") (pinfunction "SCL_6") (pintype "bidirectional"))
    )
    (net (code "44") (name "Net-(U1-~{RESET}{slash}PDI)") (class "Default")
      (node (ref "R1") (pin "1") (pinfunction "1_1") (pintype "passive"))
      (node (ref "U$1") (pin "5") (pinfunction "5_5") (pintype "passive"))
      (node (ref "U1") (pin "35") (pinfunction "~{RESET}/PDI_35") (pintype "bidirectional"))
    )
    (net (code "45") (name "Net-(U2-BST)") (class "Default")
      (node (ref "C20") (pin "1") (pinfunction "1_1") (pintype "passive"))
      (node (ref "U2") (pin "2") (pinfunction "BST_2") (pintype "passive"))
    )
    (net (code "46") (name "Net-(U2-FEEDBACK)") (class "Default")
      (node (ref "R26") (pin "1") (pinfunction "1_1") (pintype "passive"))
      (node (ref "R27") (pin "2") (pinfunction "2_2") (pintype "passive"))
      (node (ref "U2") (pin "5") (pinfunction "FEEDBACK_5") (pintype "input"))
    )
    (net (code "47") (name "Net-(U2-RCL)") (class "Default")
      (node (ref "R28") (pin "2") (pinfunction "2_2") (pintype "passive"))
      (node (ref "U2") (pin "3") (pinfunction "RCL_3") (pintype "passive"))
    )
    (net (code "48") (name "Net-(U2-RON)") (class "Default")
      (node (ref "R29") (pin "1") (pinfunction "1_1") (pintype "passive"))
      (node (ref "U2") (pin "6") (pinfunction "RON_6") (pintype "input"))
    )
    (net (code "49") (name "Net-(U2-SW)") (class "Default")
      (node (ref "C20") (pin "2") (pinfunction "2_2") (pintype "passive"))
      (node (ref "D5") (pin "C") (pinfunction "C_C") (pintype "passive"))
      (node (ref "L1") (pin "1") (pinfunction "1_1") (pintype "passive"))
      (node (ref "U2") (pin "1") (pinfunction "SW_1") (pintype "output"))
    )
    (net (code "50") (name "Net-(U2-VCC)") (class "Default")
      (node (ref "C19") (pin "1") (pinfunction "1_1") (pintype "passive"))
      (node (ref "U2") (pin "7") (pinfunction "VCC_7") (pintype "power_in"))
    )
    (net (code "51") (name "Net-(U3-BAT)") (class "Default")
      (node (ref "R13") (pin "2") (pinfunction "2_2") (pintype "passive"))
      (node (ref "R14") (pin "1") (pinfunction "1_1") (pintype "passive"))
      (node (ref "U3") (pin "4") (pinfunction "BAT_4") (pintype "bidirectional"))
    )
    (net (code "52") (name "Net-(U3-SRN)") (class "Default")
      (node (ref "C12") (pin "1") (pinfunction "1_1") (pintype "passive"))
      (node (ref "C13") (pin "2") (pinfunction "2_2") (pintype "passive"))
      (node (ref "R17") (pin "2") (pinfunction "2_2") (pintype "passive"))
      (node (ref "U3") (pin "10") (pinfunction "SRN_10") (pintype "bidirectional"))
    )
    (net (code "53") (name "Net-(U3-SRP)") (class "Default")
      (node (ref "C12") (pin "2") (pinfunction "2_2") (pintype "passive"))
      (node (ref "C14") (pin "2") (pinfunction "2_2") (pintype "passive"))
      (node (ref "R18") (pin "2") (pinfunction "2_2") (pintype "passive"))
      (node (ref "U3") (pin "9") (pinfunction "SRP_9") (pintype "bidirectional"))
    )
    (net (code "54") (name "Net-(U4-BST)") (class "Default")
      (node (ref "C17") (pin "1") (pinfunction "1_1") (pintype "passive"))
      (node (ref "U4") (pin "6") (pinfunction "BST_6") (pintype "bidirectional"))
    )
    (net (code "55") (name "Net-(U4-FB)") (class "Default")
      (node (ref "R22") (pin "2") (pinfunction "2_2") (pintype "passive"))
      (node (ref "R23") (pin "2") (pinfunction "2_2") (pintype "passive"))
      (node (ref "U4") (pin "4") (pinfunction "FB_4") (pintype "bidirectional"))
    )
    (net (code "56") (name "Net-(U4-SW)") (class "Default")
      (node (ref "C17") (pin "2") (pinfunction "2_2") (pintype "passive"))
      (node (ref "L2") (pin "1") (pinfunction "1_1") (pintype "passive"))
      (node (ref "U4") (pin "2") (pinfunction "SW_2") (pintype "bidirectional"))
    )
    (net (code "57") (name "PACK_TEMP") (class "Default")
      (node (ref "R40") (pin "2") (pinfunction "2_2") (pintype "passive"))
      (node (ref "T2_-") (pin "1") (pinfunction "P_1") (pintype "passive"))
      (node (ref "U1") (pin "43") (pinfunction "PA3_43") (pintype "bidirectional"))
      (node (ref "U6") (pin "2") (pinfunction "2_2") (pintype "passive"))
    )
    (net (code "58") (name "RX") (class "Default")
      (node (ref "R4") (pin "1") (pinfunction "1_1") (pintype "passive"))
      (node (ref "R5") (pin "2") (pinfunction "2_2") (pintype "passive"))
      (node (ref "U1") (pin "32") (pinfunction "PE2_32") (pintype "bidirectional"))
    )
    (net (code "59") (name "SCL") (class "Default")
      (node (ref "R12") (pin "1") (pinfunction "1_1") (pintype "passive"))
      (node (ref "U1") (pin "11") (pinfunction "PC1_11") (pintype "bidirectional"))
      (node (ref "U3") (pin "13") (pinfunction "P4/SCL_13") (pintype "bidirectional"))
    )
    (net (code "60") (name "SDA") (class "Default")
      (node (ref "R11") (pin "1") (pinfunction "1_1") (pintype "passive"))
      (node (ref "U1") (pin "10") (pinfunction "PC0_10") (pintype "bidirectional"))
      (node (ref "U3") (pin "14") (pinfunction "P3/SDA_14") (pintype "bidirectional"))
    )
    (net (code "61") (name "T1_+") (class "Default")
      (node (ref "C9") (pin "1") (pinfunction "1_1") (pintype "passive"))
      (node (ref "T1_+") (pin "1") (pinfunction "P_1") (pintype "passive"))
      (node (ref "U3") (pin "7") (pinfunction "REG25_7") (pintype "bidirectional"))
      (node (ref "U6") (pin "3") (pinfunction "3_3") (pintype "passive"))
    )
    (net (code "62") (name "T1_-") (class "Default")
      (node (ref "T1_-") (pin "1") (pinfunction "P_1") (pintype "passive"))
      (node (ref "U3") (pin "11") (pinfunction "P6/TS_11") (pintype "bidirectional"))
      (node (ref "U6") (pin "4") (pinfunction "4_4") (pintype "passive"))
    )
    (net (code "63") (name "TX") (class "Default")
      (node (ref "R7") (pin "2") (pinfunction "2_2") (pintype "passive"))
      (node (ref "U1") (pin "33") (pinfunction "PE3_33") (pintype "bidirectional"))
    )
    (net (code "64") (name "VCC") (class "Default")
      (node (ref "C6") (pin "+") (pinfunction "+_+") (pintype "passive"))
      (node (ref "D4") (pin "C") (pinfunction "C_C") (pintype "passive"))
      (node (ref "F1") (pin "2") (pinfunction "2_2") (pintype "passive"))
      (node (ref "R29") (pin "2") (pinfunction "2_2") (pintype "passive"))
      (node (ref "R9") (pin "2") (pinfunction "2_2") (pintype "passive"))
      (node (ref "U2") (pin "8") (pinfunction "VIN_8") (pintype "power_in"))
      (node (ref "VBUS") (pin "1") (pinfunction "1_1") (pintype "passive"))
    )
    (net (code "65") (name "VIN_SENSE") (class "Default")
      (node (ref "R10") (pin "2") (pinfunction "2_2") (pintype "passive"))
      (node (ref "R9") (pin "1") (pinfunction "1_1") (pintype "passive"))
      (node (ref "U1") (pin "41") (pinfunction "PA1_41") (pintype "bidirectional"))
    )
    (net (code "66") (name "unconnected-(U1-PA5-Pad1)") (class "Default")
      (node (ref "U1") (pin "1") (pinfunction "PA5_1") (pintype "bidirectional"))
    )
    (net (code "67") (name "unconnected-(U1-PA6-Pad2)") (class "Default")
      (node (ref "U1") (pin "2") (pinfunction "PA6_2") (pintype "bidirectional"))
    )
    (net (code "68") (name "unconnected-(U1-PA7-Pad3)") (class "Default")
      (node (ref "U1") (pin "3") (pinfunction "PA7_3") (pintype "bidirectional"))
    )
    (net (code "69") (name "unconnected-(U1-PB0-Pad4)") (class "Default")
      (node (ref "U1") (pin "4") (pinfunction "PB0_4") (pintype "bidirectional"))
    )
    (net (code "70") (name "unconnected-(U1-PB1-Pad5)") (class "Default")
      (node (ref "U1") (pin "5") (pinfunction "PB1_5") (pintype "bidirectional"))
    )
    (net (code "71") (name "unconnected-(U1-PB2-Pad6)") (class "Default")
      (node (ref "U1") (pin "6") (pinfunction "PB2_6") (pintype "bidirectional"))
    )
    (net (code "72") (name "unconnected-(U1-PB3-Pad7)") (class "Default")
      (node (ref "U1") (pin "7") (pinfunction "PB3_7") (pintype "bidirectional"))
    )
    (net (code "73") (name "unconnected-(U1-PD0-Pad20)") (class "Default")
      (node (ref "U1") (pin "20") (pinfunction "PD0_20") (pintype "bidirectional"))
    )
    (net (code "74") (name "unconnected-(U1-PD1-Pad21)") (class "Default")
      (node (ref "U1") (pin "21") (pinfunction "PD1_21") (pintype "bidirectional"))
    )
    (net (code "75") (name "unconnected-(U1-PD3-Pad23)") (class "Default")
      (node (ref "U1") (pin "23") (pinfunction "PD3_23") (pintype "bidirectional"))
    )
    (net (code "76") (name "unconnected-(U1-PD4-Pad24)") (class "Default")
      (node (ref "U1") (pin "24") (pinfunction "PD4_24") (pintype "bidirectional"))
    )
    (net (code "77") (name "unconnected-(U1-PD5-Pad25)") (class "Default")
      (node (ref "U1") (pin "25") (pinfunction "PD5_25") (pintype "bidirectional"))
    )
    (net (code "78") (name "unconnected-(U1-PD6-Pad26)") (class "Default")
      (node (ref "U1") (pin "26") (pinfunction "PD6_26") (pintype "bidirectional"))
    )
    (net (code "79") (name "unconnected-(U1-PD7-Pad27)") (class "Default")
      (node (ref "U1") (pin "27") (pinfunction "PD7_27") (pintype "bidirectional"))
    )
    (net (code "80") (name "unconnected-(U3-P5{slash}HDQ-Pad12)") (class "Default")
      (node (ref "U3") (pin "12") (pinfunction "P5/HDQ_12") (pintype "bidirectional"))
    )
    (net (code "81") (name "unconnected-(U3-VEN-Pad2)") (class "Default")
      (node (ref "U3") (pin "2") (pinfunction "VEN_2") (pintype "bidirectional"))
    )
    (net (code "82") (name "unconnected-(U5-CLKOUT-Pad7)") (class "Default")
      (node (ref "U5") (pin "7") (pinfunction "CLKOUT_7") (pintype "bidirectional"))
    )
  )
)
